# BackPage.net
KiCad netlist of a schematic drawn in Altium Designer
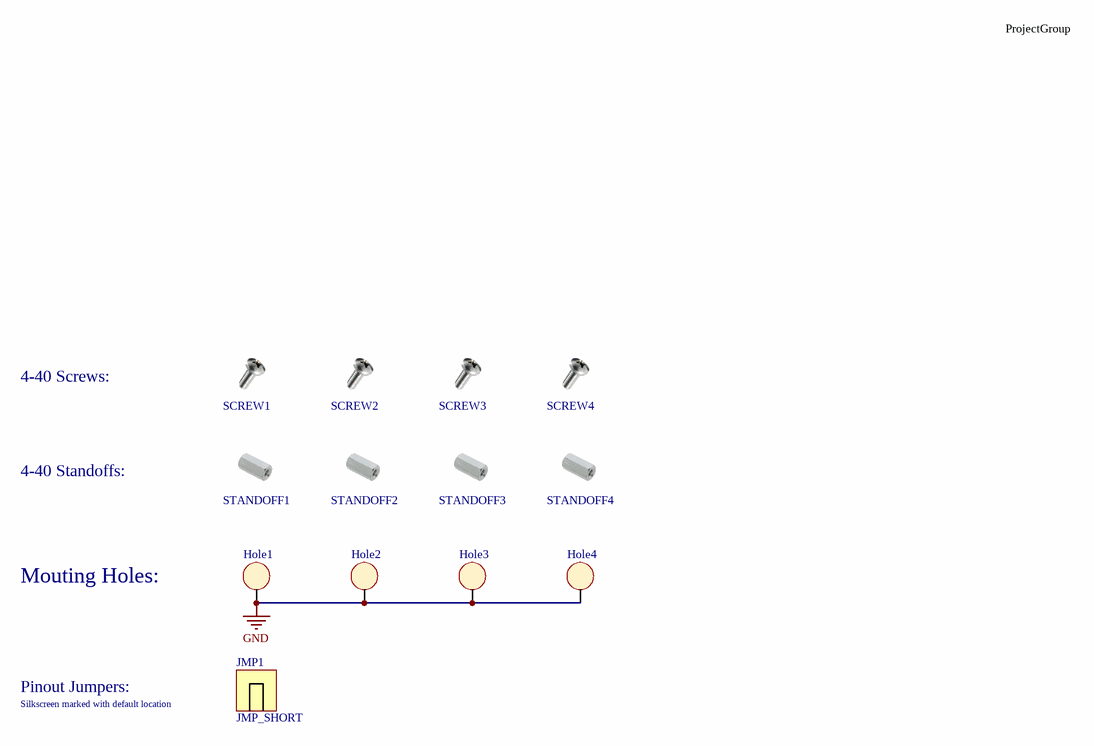
[diagram p0: BackPage.SchDoc]

(export (version "E")
  (design (tool "Eeschema 10.0.6"))
  (components
    (comp (ref "Hole1")
      (value "MOUNT_HOLE")
      (footprint "MOUNTING_HOLE")
      (description "MOUNTING HOLE")
      (libsource (lib "AMDC") (part "MOUNT_HOLE"))
    )
    (comp (ref "Hole2")
      (value "MOUNT_HOLE")
      (footprint "MOUNTING_HOLE")
      (description "MOUNTING HOLE")
      (libsource (lib "AMDC") (part "MOUNT_HOLE"))
    )
    (comp (ref "Hole3")
      (value "MOUNT_HOLE")
      (footprint "MOUNTING_HOLE")
      (description "MOUNTING HOLE")
      (libsource (lib "AMDC") (part "MOUNT_HOLE"))
    )
    (comp (ref "Hole4")
      (value "MOUNT_HOLE")
      (footprint "MOUNTING_HOLE")
      (description "MOUNTING HOLE")
      (libsource (lib "AMDC") (part "MOUNT_HOLE"))
    )
    (comp (ref "JMP1")
      (value "JMP_SHORT")
      (description "CONN JUMPER SHORTING .100\" GOLD")
      (libsource (lib "DAC") (part "JUMPER_SHORT"))
    )
    (comp (ref "SCREW1")
      (value "9900")
      (description "#4-40 Pan Head Machine Screw Phillips Drive Stainless Steel")
      (libsource (lib "DAC") (part "SCREW 4-40"))
    )
    (comp (ref "SCREW2")
      (value "9900")
      (description "#4-40 Pan Head Machine Screw Phillips Drive Stainless Steel")
      (libsource (lib "DAC") (part "SCREW 4-40"))
    )
    (comp (ref "SCREW3")
      (value "9900")
      (description "#4-40 Pan Head Machine Screw Phillips Drive Stainless Steel")
      (libsource (lib "DAC") (part "SCREW 4-40"))
    )
    (comp (ref "SCREW4")
      (value "9900")
      (description "#4-40 Pan Head Machine Screw Phillips Drive Stainless Steel")
      (libsource (lib "DAC") (part "SCREW 4-40"))
    )
    (comp (ref "STANDOFF1")
      (value "2057-440-AL-7")
      (description "Hex Standoff Threaded #4-40 Aluminum 0.500\" (12.70mm) 1/2\"")
      (libsource (lib "DAC") (part "Standoff 4-40"))
    )
    (comp (ref "STANDOFF2")
      (value "2057-440-AL-7")
      (description "Hex Standoff Threaded #4-40 Aluminum 0.500\" (12.70mm) 1/2\"")
      (libsource (lib "DAC") (part "Standoff 4-40"))
    )
    (comp (ref "STANDOFF3")
      (value "2057-440-AL-7")
      (description "Hex Standoff Threaded #4-40 Aluminum 0.500\" (12.70mm) 1/2\"")
      (libsource (lib "DAC") (part "Standoff 4-40"))
    )
    (comp (ref "STANDOFF4")
      (value "2057-440-AL-7")
      (description "Hex Standoff Threaded #4-40 Aluminum 0.500\" (12.70mm) 1/2\"")
      (libsource (lib "DAC") (part "Standoff 4-40"))
    )
  )
  (nets
    (net (code "1") (name "GND") (class "Default")
      (node (ref "Hole1") (pin "1") (pinfunction "1_1") (pintype "passive"))
      (node (ref "Hole2") (pin "1") (pinfunction "1_1") (pintype "passive"))
      (node (ref "Hole3") (pin "1") (pinfunction "1_1") (pintype "passive"))
      (node (ref "Hole4") (pin "1") (pinfunction "1_1") (pintype "passive"))
    )
  )
)
